# MECH.net
KiCad netlist of a schematic drawn in Altium Designer
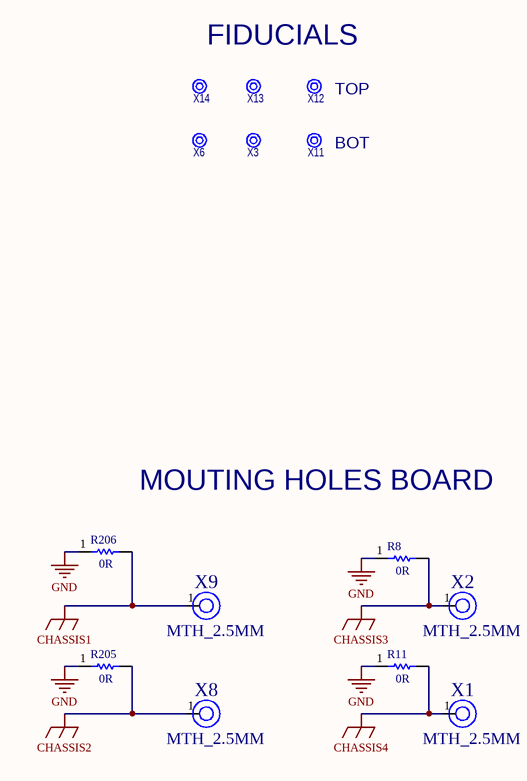
[diagram p0: MECH.SchDoc]

(export (version "E")
  (design (tool "Eeschema 10.0.6"))
  (components
    (comp (ref "R8")
      (value "0R")
      (footprint "0402")
      (fields
        (field (name "MANUFACTURER") "Vishay Dale")
        (field (name "MANUFACTURER PART NUMBER") "RCS04020000Z0ED")
      )
      (libsource (lib "IHMC_Altium_Lib") (part "0R_1/5W_0402_RCS04020000Z0ED_RES"))
    )
    (comp (ref "R11")
      (value "0R")
      (footprint "0402")
      (fields
        (field (name "MANUFACTURER") "Vishay Dale")
        (field (name "MANUFACTURER PART NUMBER") "RCS04020000Z0ED")
      )
      (libsource (lib "IHMC_Altium_Lib") (part "0R_1/5W_0402_RCS04020000Z0ED_RES"))
    )
    (comp (ref "R205")
      (value "0R")
      (footprint "0402")
      (fields
        (field (name "MANUFACTURER") "Vishay Dale")
        (field (name "MANUFACTURER PART NUMBER") "RCS04020000Z0ED")
      )
      (libsource (lib "IHMC_Altium_Lib") (part "0R_1/5W_0402_RCS04020000Z0ED_RES"))
    )
    (comp (ref "R206")
      (value "0R")
      (footprint "0402")
      (fields
        (field (name "MANUFACTURER") "Vishay Dale")
        (field (name "MANUFACTURER PART NUMBER") "RCS04020000Z0ED")
      )
      (libsource (lib "IHMC_Altium_Lib") (part "0R_1/5W_0402_RCS04020000Z0ED_RES"))
    )
    (comp (ref "X1")
      (value "MTH_2.5MM")
      (footprint "MTH-M2.5mm - CHASSIS")
      (fields (field (name "PKG_TYPE") "MTH_2.5MM"))
      (libsource (lib "IHMC_Altium_Lib") (part "MTH_2.5MM"))
    )
    (comp (ref "X2")
      (value "MTH_2.5MM")
      (footprint "MTH-M2.5mm - CHASSIS")
      (fields (field (name "PKG_TYPE") "MTH_2.5MM"))
      (libsource (lib "IHMC_Altium_Lib") (part "MTH_2.5MM"))
    )
    (comp (ref "X3")
      (value "FIDUCIAL")
      (footprint "FIDUCIAL")
      (libsource (lib "IHMC_Altium_Lib") (part "FIDUCIAL"))
    )
    (comp (ref "X6")
      (value "FIDUCIAL")
      (footprint "FIDUCIAL")
      (libsource (lib "IHMC_Altium_Lib") (part "FIDUCIAL"))
    )
    (comp (ref "X8")
      (value "MTH_2.5MM")
      (footprint "MTH-M2.5mm - CHASSIS")
      (fields (field (name "PKG_TYPE") "MTH_2.5MM"))
      (libsource (lib "IHMC_Altium_Lib") (part "MTH_2.5MM"))
    )
    (comp (ref "X9")
      (value "MTH_2.5MM")
      (footprint "MTH-M2.5mm - CHASSIS")
      (fields (field (name "PKG_TYPE") "MTH_2.5MM"))
      (libsource (lib "IHMC_Altium_Lib") (part "MTH_2.5MM"))
    )
    (comp (ref "X11")
      (value "FIDUCIAL")
      (footprint "FIDUCIAL")
      (libsource (lib "IHMC_Altium_Lib") (part "FIDUCIAL"))
    )
    (comp (ref "X12")
      (value "FIDUCIAL")
      (footprint "FIDUCIAL")
      (libsource (lib "IHMC_Altium_Lib") (part "FIDUCIAL"))
    )
    (comp (ref "X13")
      (value "FIDUCIAL")
      (footprint "FIDUCIAL")
      (libsource (lib "IHMC_Altium_Lib") (part "FIDUCIAL"))
    )
    (comp (ref "X14")
      (value "FIDUCIAL")
      (footprint "FIDUCIAL")
      (libsource (lib "IHMC_Altium_Lib") (part "FIDUCIAL"))
    )
  )
  (nets
    (net (code "1") (name "CHASSIS1") (class "Default")
      (node (ref "R206") (pin "2") (pinfunction "2_2") (pintype "passive"))
      (node (ref "X9") (pin "1") (pinfunction "1_1") (pintype "passive"))
    )
    (net (code "2") (name "CHASSIS2") (class "Default")
      (node (ref "R205") (pin "2") (pinfunction "2_2") (pintype "passive"))
      (node (ref "X8") (pin "1") (pinfunction "1_1") (pintype "passive"))
    )
    (net (code "3") (name "CHASSIS3") (class "Default")
      (node (ref "R8") (pin "2") (pinfunction "2_2") (pintype "passive"))
      (node (ref "X2") (pin "1") (pinfunction "1_1") (pintype "passive"))
    )
    (net (code "4") (name "CHASSIS4") (class "Default")
      (node (ref "R11") (pin "2") (pinfunction "2_2") (pintype "passive"))
      (node (ref "X1") (pin "1") (pinfunction "1_1") (pintype "passive"))
    )
    (net (code "5") (name "GND") (class "Default")
      (node (ref "R11") (pin "1") (pinfunction "1_1") (pintype "passive"))
      (node (ref "R205") (pin "1") (pinfunction "1_1") (pintype "passive"))
      (node (ref "R206") (pin "1") (pinfunction "1_1") (pintype "passive"))
      (node (ref "R8") (pin "1") (pinfunction "1_1") (pintype "passive"))
    )
  )
)
